# BrushedESC.net
KiCad netlist of a schematic drawn in Altium Designer
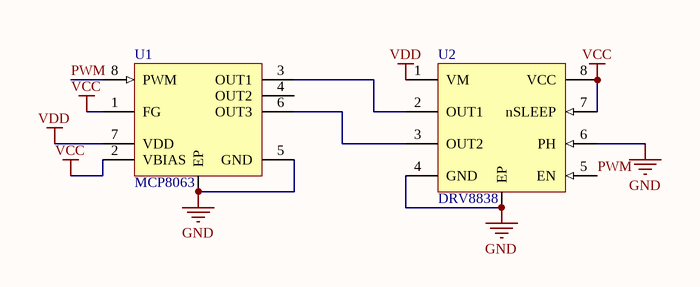
[diagram p0: BrushedESC.SchDoc]

(export (version "E")
  (design (tool "Eeschema 10.0.6"))
  (components
    (comp (ref "U1")
      (value "MCP8063")
      (footprint "DFN8")
      (fields (field (name "PARTNUMBER") "MTD6501G-HC1") (field (name "MANUFACTURER") "Microchip"))
      (libsource (lib "Components") (part "MCP8063"))
    )
    (comp (ref "U2")
      (value "DRV8838")
      (footprint "SON50P200X80_HS-9N")
      (fields (field (name "PARTNUMBER") "MTD6501G-HC1") (field (name "MANUFACTURER") "Microchip"))
      (libsource (lib "Components") (part "DRV8838"))
    )
  )
  (nets
    (net (code "1") (name "/PWM") (class "Default")
      (node (ref "U1") (pin "8") (pinfunction "PWM_8") (pintype "input"))
      (node (ref "U2") (pin "5") (pinfunction "EN_5") (pintype "input"))
    )
    (net (code "2") (name "GND") (class "Default")
      (node (ref "U1") (pin "5") (pinfunction "GND_5") (pintype "power_in"))
      (node (ref "U1") (pin "9") (pinfunction "EP_9") (pintype "passive"))
      (node (ref "U2") (pin "4") (pinfunction "GND_4") (pintype "power_in"))
      (node (ref "U2") (pin "6") (pinfunction "PH_6") (pintype "input"))
      (node (ref "U2") (pin "9") (pinfunction "EP_9") (pintype "passive"))
    )
    (net (code "3") (name "Net-(U1-OUT1)") (class "Default")
      (node (ref "U1") (pin "3") (pinfunction "OUT1_3") (pintype "tri_state"))
      (node (ref "U2") (pin "2") (pinfunction "OUT1_2") (pintype "tri_state"))
    )
    (net (code "4") (name "Net-(U1-OUT3)") (class "Default")
      (node (ref "U1") (pin "6") (pinfunction "OUT3_6") (pintype "tri_state"))
      (node (ref "U2") (pin "3") (pinfunction "OUT2_3") (pintype "tri_state"))
    )
    (net (code "5") (name "VCC") (class "Default")
      (node (ref "U1") (pin "1") (pinfunction "FG_1") (pintype "tri_state"))
      (node (ref "U1") (pin "2") (pinfunction "VBIAS_2") (pintype "power_in"))
      (node (ref "U2") (pin "7") (pinfunction "nSLEEP_7") (pintype "input"))
      (node (ref "U2") (pin "8") (pinfunction "VCC_8") (pintype "power_in"))
    )
    (net (code "6") (name "VDD") (class "Default")
      (node (ref "U1") (pin "7") (pinfunction "VDD_7") (pintype "power_in"))
      (node (ref "U2") (pin "1") (pinfunction "VM_1") (pintype "power_in"))
    )
    (net (code "7") (name "unconnected-(U1-OUT2-Pad4)") (class "Default")
      (node (ref "U1") (pin "4") (pinfunction "OUT2_4") (pintype "tri_state"))
    )
  )
)
